# armedbase.net
KiCad netlist of a schematic drawn in EAGLE
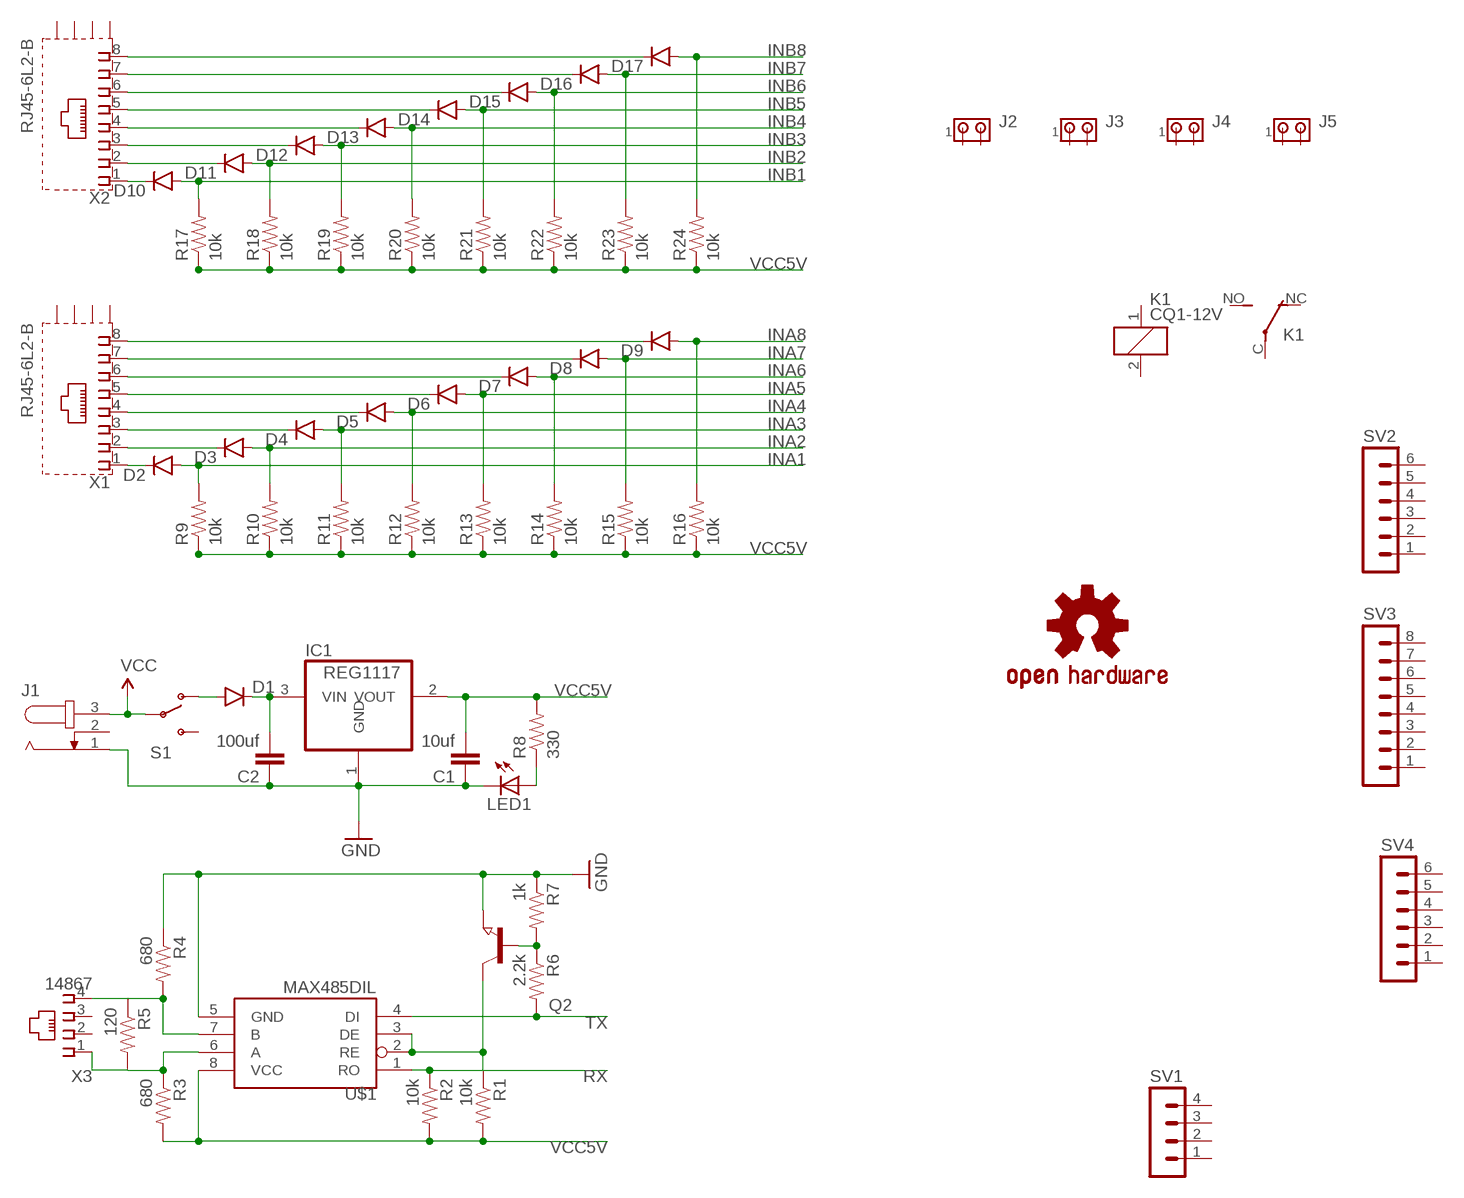
[diagram p0: schematic, sheet 1]

(export (version "E")
  (design (tool "Eeschema 10.0.6"))
  (components
    (comp (ref "C1")
      (value "10uf")
      (footprint "eagle-import:0805")
      (libsource (lib "eagle-import") (part "CAP0805"))
    )
    (comp (ref "C2")
      (value "100uf")
      (footprint "eagle-import:0805")
      (libsource (lib "eagle-import") (part "CAP0805"))
    )
    (comp (ref "D1")
      (value "DIODESMA")
      (footprint "eagle-import:SMA-DIODE")
      (libsource (lib "eagle-import") (part "DIODESMA"))
    )
    (comp (ref "D2")
      (value "DIODESMA")
      (footprint "eagle-import:SMA-DIODE")
      (libsource (lib "eagle-import") (part "DIODESMA"))
    )
    (comp (ref "D3")
      (value "DIODESMA")
      (footprint "eagle-import:SMA-DIODE")
      (libsource (lib "eagle-import") (part "DIODESMA"))
    )
    (comp (ref "D4")
      (value "DIODESMA")
      (footprint "eagle-import:SMA-DIODE")
      (libsource (lib "eagle-import") (part "DIODESMA"))
    )
    (comp (ref "D5")
      (value "DIODESMA")
      (footprint "eagle-import:SMA-DIODE")
      (libsource (lib "eagle-import") (part "DIODESMA"))
    )
    (comp (ref "D6")
      (value "DIODESMA")
      (footprint "eagle-import:SMA-DIODE")
      (libsource (lib "eagle-import") (part "DIODESMA"))
    )
    (comp (ref "D7")
      (value "DIODESMA")
      (footprint "eagle-import:SMA-DIODE")
      (libsource (lib "eagle-import") (part "DIODESMA"))
    )
    (comp (ref "D8")
      (value "DIODESMA")
      (footprint "eagle-import:SMA-DIODE")
      (libsource (lib "eagle-import") (part "DIODESMA"))
    )
    (comp (ref "D9")
      (value "DIODESMA")
      (footprint "eagle-import:SMA-DIODE")
      (libsource (lib "eagle-import") (part "DIODESMA"))
    )
    (comp (ref "D10")
      (value "DIODESMA")
      (footprint "eagle-import:SMA-DIODE")
      (libsource (lib "eagle-import") (part "DIODESMA"))
    )
    (comp (ref "D11")
      (value "DIODESMA")
      (footprint "eagle-import:SMA-DIODE")
      (libsource (lib "eagle-import") (part "DIODESMA"))
    )
    (comp (ref "D12")
      (value "DIODESMA")
      (footprint "eagle-import:SMA-DIODE")
      (libsource (lib "eagle-import") (part "DIODESMA"))
    )
    (comp (ref "D13")
      (value "DIODESMA")
      (footprint "eagle-import:SMA-DIODE")
      (libsource (lib "eagle-import") (part "DIODESMA"))
    )
    (comp (ref "D14")
      (value "DIODESMA")
      (footprint "eagle-import:SMA-DIODE")
      (libsource (lib "eagle-import") (part "DIODESMA"))
    )
    (comp (ref "D15")
      (value "DIODESMA")
      (footprint "eagle-import:SMA-DIODE")
      (libsource (lib "eagle-import") (part "DIODESMA"))
    )
    (comp (ref "D16")
      (value "DIODESMA")
      (footprint "eagle-import:SMA-DIODE")
      (libsource (lib "eagle-import") (part "DIODESMA"))
    )
    (comp (ref "D17")
      (value "DIODESMA")
      (footprint "eagle-import:SMA-DIODE")
      (libsource (lib "eagle-import") (part "DIODESMA"))
    )
    (comp (ref "IC1")
      (value "REG1117")
      (footprint "eagle-import:SOT223")
      (libsource (lib "eagle-import") (part "REG1117"))
    )
    (comp (ref "J1")
      (value "JACK-PLUG1")
      (footprint "eagle-import:SPC4078")
      (libsource (lib "eagle-import") (part "JACK-PLUG1"))
    )
    (comp (ref "J2")
      (value "MTA02-156")
      (footprint "eagle-import:1X2MTA")
      (libsource (lib "eagle-import") (part "MTA02-156"))
    )
    (comp (ref "J3")
      (value "MTA02-156")
      (footprint "eagle-import:1X2MTA")
      (libsource (lib "eagle-import") (part "MTA02-156"))
    )
    (comp (ref "J4")
      (value "MTA02-156")
      (footprint "eagle-import:1X2MTA")
      (libsource (lib "eagle-import") (part "MTA02-156"))
    )
    (comp (ref "J5")
      (value "MTA02-156")
      (footprint "eagle-import:1X2MTA")
      (libsource (lib "eagle-import") (part "MTA02-156"))
    )
    (comp (ref "K1")
      (value "CQ1-12V")
      (footprint "eagle-import:CQ1")
      (libsource (lib "eagle-import") (part "CQ1-12V"))
    )
    (comp (ref "LED1")
      (value "LEDCHIP-LED0805")
      (footprint "eagle-import:CHIP-LED0805")
      (libsource (lib "eagle-import") (part "LEDCHIP-LED0805"))
    )
    (comp (ref "LOGO2")
      (value "OSHW-LOGOL")
      (footprint "eagle-import:OSHW-LOGO-L")
      (libsource (lib "eagle-import") (part "OSHW-LOGOL"))
    )
    (comp (ref "Q2")
      (value "NPN-TRANSISTOR_SOT23")
      (footprint "eagle-import:SOT23")
      (libsource (lib "eagle-import") (part "NPN-TRANSISTOR_SOT23"))
    )
    (comp (ref "R1")
      (value "10k")
      (footprint "eagle-import:0805")
      (libsource (lib "eagle-import") (part "RESISTOR0805-RES"))
    )
    (comp (ref "R2")
      (value "10k")
      (footprint "eagle-import:0805")
      (libsource (lib "eagle-import") (part "RESISTOR0805-RES"))
    )
    (comp (ref "R3")
      (value "680")
      (footprint "eagle-import:0805")
      (libsource (lib "eagle-import") (part "RESISTOR0805-RES"))
    )
    (comp (ref "R4")
      (value "680")
      (footprint "eagle-import:0805")
      (libsource (lib "eagle-import") (part "RESISTOR0805-RES"))
    )
    (comp (ref "R5")
      (value "120")
      (footprint "eagle-import:0805")
      (libsource (lib "eagle-import") (part "RESISTOR0805-RES"))
    )
    (comp (ref "R6")
      (value "2.2k")
      (footprint "eagle-import:0805")
      (libsource (lib "eagle-import") (part "RESISTOR0805-RES"))
    )
    (comp (ref "R7")
      (value "1k")
      (footprint "eagle-import:0805")
      (libsource (lib "eagle-import") (part "RESISTOR0805-RES"))
    )
    (comp (ref "R8")
      (value "330")
      (footprint "eagle-import:0805")
      (libsource (lib "eagle-import") (part "RESISTOR0805-RES"))
    )
    (comp (ref "R9")
      (value "10k")
      (footprint "eagle-import:0805")
      (libsource (lib "eagle-import") (part "RESISTOR0805-RES"))
    )
    (comp (ref "R10")
      (value "10k")
      (footprint "eagle-import:0805")
      (libsource (lib "eagle-import") (part "RESISTOR0805-RES"))
    )
    (comp (ref "R11")
      (value "10k")
      (footprint "eagle-import:0805")
      (libsource (lib "eagle-import") (part "RESISTOR0805-RES"))
    )
    (comp (ref "R12")
      (value "10k")
      (footprint "eagle-import:0805")
      (libsource (lib "eagle-import") (part "RESISTOR0805-RES"))
    )
    (comp (ref "R13")
      (value "10k")
      (footprint "eagle-import:0805")
      (libsource (lib "eagle-import") (part "RESISTOR0805-RES"))
    )
    (comp (ref "R14")
      (value "10k")
      (footprint "eagle-import:0805")
      (libsource (lib "eagle-import") (part "RESISTOR0805-RES"))
    )
    (comp (ref "R15")
      (value "10k")
      (footprint "eagle-import:0805")
      (libsource (lib "eagle-import") (part "RESISTOR0805-RES"))
    )
    (comp (ref "R16")
      (value "10k")
      (footprint "eagle-import:0805")
      (libsource (lib "eagle-import") (part "RESISTOR0805-RES"))
    )
    (comp (ref "R17")
      (value "10k")
      (footprint "eagle-import:0805")
      (libsource (lib "eagle-import") (part "RESISTOR0805-RES"))
    )
    (comp (ref "R18")
      (value "10k")
      (footprint "eagle-import:0805")
      (libsource (lib "eagle-import") (part "RESISTOR0805-RES"))
    )
    (comp (ref "R19")
      (value "10k")
      (footprint "eagle-import:0805")
      (libsource (lib "eagle-import") (part "RESISTOR0805-RES"))
    )
    (comp (ref "R20")
      (value "10k")
      (footprint "eagle-import:0805")
      (libsource (lib "eagle-import") (part "RESISTOR0805-RES"))
    )
    (comp (ref "R21")
      (value "10k")
      (footprint "eagle-import:0805")
      (libsource (lib "eagle-import") (part "RESISTOR0805-RES"))
    )
    (comp (ref "R22")
      (value "10k")
      (footprint "eagle-import:0805")
      (libsource (lib "eagle-import") (part "RESISTOR0805-RES"))
    )
    (comp (ref "R23")
      (value "10k")
      (footprint "eagle-import:0805")
      (libsource (lib "eagle-import") (part "RESISTOR0805-RES"))
    )
    (comp (ref "R24")
      (value "10k")
      (footprint "eagle-import:0805")
      (libsource (lib "eagle-import") (part "RESISTOR0805-RES"))
    )
    (comp (ref "S1")
      (value "SWITCH-SPDTSMD2")
      (footprint "eagle-import:SWITCH-SPDT-SMD")
      (libsource (lib "eagle-import") (part "SWITCH-SPDTSMD2"))
    )
    (comp (ref "SV1")
      (value "MA04-1")
      (footprint "eagle-import:MA04-1")
      (libsource (lib "eagle-import") (part "MA04-1"))
    )
    (comp (ref "SV2")
      (value "MA06-1")
      (footprint "eagle-import:MA06-1")
      (libsource (lib "eagle-import") (part "MA06-1"))
    )
    (comp (ref "SV3")
      (value "MA08-1")
      (footprint "eagle-import:MA08-1")
      (libsource (lib "eagle-import") (part "MA08-1"))
    )
    (comp (ref "SV4")
      (value "MA06-1")
      (footprint "eagle-import:MA06-1")
      (libsource (lib "eagle-import") (part "MA06-1"))
    )
    (comp (ref "U$1")
      (value "MAX485DIL")
      (footprint "eagle-import:DIL08")
      (libsource (lib "eagle-import") (part "MAX485DIL"))
    )
    (comp (ref "X1")
      (value "RJ45-6L2-B")
      (footprint "eagle-import:RJ45-SHIELD2")
      (libsource (lib "eagle-import") (part "RJ452-B-6L"))
    )
    (comp (ref "X2")
      (value "RJ45-6L2-B")
      (footprint "eagle-import:RJ45-SHIELD2")
      (libsource (lib "eagle-import") (part "RJ452-B-6L"))
    )
    (comp (ref "X3")
      (value "14867")
      (footprint "eagle-import:14867")
      (libsource (lib "eagle-import") (part "14867"))
    )
  )
  (nets
    (net (code "1") (name "/INA1") (class "Default")
      (node (ref "D2") (pin "A") (pinfunction "A_A") (pintype "passive"))
      (node (ref "R9") (pin "2") (pinfunction "2_2") (pintype "passive"))
    )
    (net (code "2") (name "/INA2") (class "Default")
      (node (ref "D3") (pin "A") (pinfunction "A_A") (pintype "passive"))
      (node (ref "R10") (pin "2") (pinfunction "2_2") (pintype "passive"))
    )
    (net (code "3") (name "/INA3") (class "Default")
      (node (ref "D4") (pin "A") (pinfunction "A_A") (pintype "passive"))
      (node (ref "R11") (pin "2") (pinfunction "2_2") (pintype "passive"))
    )
    (net (code "4") (name "/INA4") (class "Default")
      (node (ref "D5") (pin "A") (pinfunction "A_A") (pintype "passive"))
      (node (ref "R12") (pin "2") (pinfunction "2_2") (pintype "passive"))
    )
    (net (code "5") (name "/INA5") (class "Default")
      (node (ref "D6") (pin "A") (pinfunction "A_A") (pintype "passive"))
      (node (ref "R13") (pin "2") (pinfunction "2_2") (pintype "passive"))
    )
    (net (code "6") (name "/INA6") (class "Default")
      (node (ref "D7") (pin "A") (pinfunction "A_A") (pintype "passive"))
      (node (ref "R14") (pin "2") (pinfunction "2_2") (pintype "passive"))
    )
    (net (code "7") (name "/INA7") (class "Default")
      (node (ref "D8") (pin "A") (pinfunction "A_A") (pintype "passive"))
      (node (ref "R15") (pin "2") (pinfunction "2_2") (pintype "passive"))
    )
    (net (code "8") (name "/INA8") (class "Default")
      (node (ref "D9") (pin "A") (pinfunction "A_A") (pintype "passive"))
      (node (ref "R16") (pin "2") (pinfunction "2_2") (pintype "passive"))
    )
    (net (code "9") (name "/INB1") (class "Default")
      (node (ref "D10") (pin "A") (pinfunction "A_A") (pintype "passive"))
      (node (ref "R17") (pin "2") (pinfunction "2_2") (pintype "passive"))
    )
    (net (code "10") (name "/INB2") (class "Default")
      (node (ref "D11") (pin "A") (pinfunction "A_A") (pintype "passive"))
      (node (ref "R18") (pin "2") (pinfunction "2_2") (pintype "passive"))
    )
    (net (code "11") (name "/INB3") (class "Default")
      (node (ref "D12") (pin "A") (pinfunction "A_A") (pintype "passive"))
      (node (ref "R19") (pin "2") (pinfunction "2_2") (pintype "passive"))
    )
    (net (code "12") (name "/INB4") (class "Default")
      (node (ref "D13") (pin "A") (pinfunction "A_A") (pintype "passive"))
      (node (ref "R20") (pin "2") (pinfunction "2_2") (pintype "passive"))
    )
    (net (code "13") (name "/INB5") (class "Default")
      (node (ref "D14") (pin "A") (pinfunction "A_A") (pintype "passive"))
      (node (ref "R21") (pin "2") (pinfunction "2_2") (pintype "passive"))
    )
    (net (code "14") (name "/INB6") (class "Default")
      (node (ref "D15") (pin "A") (pinfunction "A_A") (pintype "passive"))
      (node (ref "R22") (pin "2") (pinfunction "2_2") (pintype "passive"))
    )
    (net (code "15") (name "/INB7") (class "Default")
      (node (ref "D16") (pin "A") (pinfunction "A_A") (pintype "passive"))
      (node (ref "R23") (pin "2") (pinfunction "2_2") (pintype "passive"))
    )
    (net (code "16") (name "/INB8") (class "Default")
      (node (ref "D17") (pin "A") (pinfunction "A_A") (pintype "passive"))
      (node (ref "R24") (pin "2") (pinfunction "2_2") (pintype "passive"))
    )
    (net (code "17") (name "/RX") (class "Default")
      (node (ref "R2") (pin "1") (pinfunction "1_1") (pintype "passive"))
      (node (ref "U$1") (pin "1") (pinfunction "RO_1") (pintype "bidirectional"))
    )
    (net (code "18") (name "/TX") (class "Default")
      (node (ref "R6") (pin "2") (pinfunction "2_2") (pintype "passive"))
      (node (ref "U$1") (pin "4") (pinfunction "DI_4") (pintype "bidirectional"))
    )
    (net (code "19") (name "/VCC5V") (class "Default")
      (node (ref "C1") (pin "2") (pinfunction "2_2") (pintype "passive"))
      (node (ref "IC1") (pin "2") (pinfunction "VOUT_2") (pintype "output"))
      (node (ref "R1") (pin "2") (pinfunction "2_2") (pintype "passive"))
      (node (ref "R10") (pin "1") (pinfunction "1_1") (pintype "passive"))
      (node (ref "R11") (pin "1") (pinfunction "1_1") (pintype "passive"))
      (node (ref "R12") (pin "1") (pinfunction "1_1") (pintype "passive"))
      (node (ref "R13") (pin "1") (pinfunction "1_1") (pintype "passive"))
      (node (ref "R14") (pin "1") (pinfunction "1_1") (pintype "passive"))
      (node (ref "R15") (pin "1") (pinfunction "1_1") (pintype "passive"))
      (node (ref "R16") (pin "1") (pinfunction "1_1") (pintype "passive"))
      (node (ref "R17") (pin "1") (pinfunction "1_1") (pintype "passive"))
      (node (ref "R18") (pin "1") (pinfunction "1_1") (pintype "passive"))
      (node (ref "R19") (pin "1") (pinfunction "1_1") (pintype "passive"))
      (node (ref "R2") (pin "2") (pinfunction "2_2") (pintype "passive"))
      (node (ref "R20") (pin "1") (pinfunction "1_1") (pintype "passive"))
      (node (ref "R21") (pin "1") (pinfunction "1_1") (pintype "passive"))
      (node (ref "R22") (pin "1") (pinfunction "1_1") (pintype "passive"))
      (node (ref "R23") (pin "1") (pinfunction "1_1") (pintype "passive"))
      (node (ref "R24") (pin "1") (pinfunction "1_1") (pintype "passive"))
      (node (ref "R3") (pin "2") (pinfunction "2_2") (pintype "passive"))
      (node (ref "R8") (pin "2") (pinfunction "2_2") (pintype "passive"))
      (node (ref "R9") (pin "1") (pinfunction "1_1") (pintype "passive"))
      (node (ref "U$1") (pin "8") (pinfunction "VCC_8") (pintype "bidirectional"))
    )
    (net (code "20") (name "GND") (class "Default")
      (node (ref "C1") (pin "1") (pinfunction "1_1") (pintype "passive"))
      (node (ref "C2") (pin "1") (pinfunction "1_1") (pintype "passive"))
      (node (ref "IC1") (pin "1") (pinfunction "GND_1") (pintype "power_in"))
      (node (ref "J1") (pin "1") (pinfunction "1_1") (pintype "passive"))
      (node (ref "LED1") (pin "C") (pinfunction "C_C") (pintype "passive"))
      (node (ref "Q2") (pin "2") (pinfunction "E_2") (pintype "passive"))
      (node (ref "R4") (pin "1") (pinfunction "1_1") (pintype "passive"))
      (node (ref "R7") (pin "1") (pinfunction "1_1") (pintype "passive"))
      (node (ref "U$1") (pin "5") (pinfunction "GND_5") (pintype "bidirectional"))
    )
    (net (code "21") (name "Net-(D2-PadC)") (class "Default")
      (node (ref "D2") (pin "C") (pinfunction "C_C") (pintype "passive"))
      (node (ref "X1") (pin "1") (pinfunction "1_1") (pintype "passive"))
    )
    (net (code "22") (name "Net-(D3-PadC)") (class "Default")
      (node (ref "D3") (pin "C") (pinfunction "C_C") (pintype "passive"))
      (node (ref "X1") (pin "2") (pinfunction "2_2") (pintype "passive"))
    )
    (net (code "23") (name "Net-(D4-PadC)") (class "Default")
      (node (ref "D4") (pin "C") (pinfunction "C_C") (pintype "passive"))
      (node (ref "X1") (pin "3") (pinfunction "3_3") (pintype "passive"))
    )
    (net (code "24") (name "Net-(D5-PadC)") (class "Default")
      (node (ref "D5") (pin "C") (pinfunction "C_C") (pintype "passive"))
      (node (ref "X1") (pin "4") (pinfunction "4_4") (pintype "passive"))
    )
    (net (code "25") (name "Net-(D6-PadC)") (class "Default")
      (node (ref "D6") (pin "C") (pinfunction "C_C") (pintype "passive"))
      (node (ref "X1") (pin "5") (pinfunction "5_5") (pintype "passive"))
    )
    (net (code "26") (name "Net-(D7-PadC)") (class "Default")
      (node (ref "D7") (pin "C") (pinfunction "C_C") (pintype "passive"))
      (node (ref "X1") (pin "6") (pinfunction "6_6") (pintype "passive"))
    )
    (net (code "27") (name "Net-(D8-PadC)") (class "Default")
      (node (ref "D8") (pin "C") (pinfunction "C_C") (pintype "passive"))
      (node (ref "X1") (pin "7") (pinfunction "7_7") (pintype "passive"))
    )
    (net (code "28") (name "Net-(D9-PadC)") (class "Default")
      (node (ref "D9") (pin "C") (pinfunction "C_C") (pintype "passive"))
      (node (ref "X1") (pin "8") (pinfunction "8_8") (pintype "passive"))
    )
    (net (code "29") (name "Net-(D10-PadC)") (class "Default")
      (node (ref "D10") (pin "C") (pinfunction "C_C") (pintype "passive"))
      (node (ref "X2") (pin "1") (pinfunction "1_1") (pintype "passive"))
    )
    (net (code "30") (name "Net-(D11-PadC)") (class "Default")
      (node (ref "D11") (pin "C") (pinfunction "C_C") (pintype "passive"))
      (node (ref "X2") (pin "2") (pinfunction "2_2") (pintype "passive"))
    )
    (net (code "31") (name "Net-(D12-PadC)") (class "Default")
      (node (ref "D12") (pin "C") (pinfunction "C_C") (pintype "passive"))
      (node (ref "X2") (pin "3") (pinfunction "3_3") (pintype "passive"))
    )
    (net (code "32") (name "Net-(D13-PadC)") (class "Default")
      (node (ref "D13") (pin "C") (pinfunction "C_C") (pintype "passive"))
      (node (ref "X2") (pin "4") (pinfunction "4_4") (pintype "passive"))
    )
    (net (code "33") (name "Net-(D14-PadC)") (class "Default")
      (node (ref "D14") (pin "C") (pinfunction "C_C") (pintype "passive"))
      (node (ref "X2") (pin "5") (pinfunction "5_5") (pintype "passive"))
    )
    (net (code "34") (name "Net-(D15-PadC)") (class "Default")
      (node (ref "D15") (pin "C") (pinfunction "C_C") (pintype "passive"))
      (node (ref "X2") (pin "6") (pinfunction "6_6") (pintype "passive"))
    )
    (net (code "35") (name "Net-(D16-PadC)") (class "Default")
      (node (ref "D16") (pin "C") (pinfunction "C_C") (pintype "passive"))
      (node (ref "X2") (pin "7") (pinfunction "7_7") (pintype "passive"))
    )
    (net (code "36") (name "Net-(D17-PadC)") (class "Default")
      (node (ref "D17") (pin "C") (pinfunction "C_C") (pintype "passive"))
      (node (ref "X2") (pin "8") (pinfunction "8_8") (pintype "passive"))
    )
    (net (code "37") (name "Net-(IC1-VIN)") (class "Default")
      (node (ref "C2") (pin "2") (pinfunction "2_2") (pintype "passive"))
      (node (ref "D1") (pin "C") (pinfunction "C_C") (pintype "passive"))
      (node (ref "IC1") (pin "3") (pinfunction "VIN_3") (pintype "input"))
    )
    (net (code "38") (name "Net-(LED1-PadA)") (class "Default")
      (node (ref "LED1") (pin "A") (pinfunction "A_A") (pintype "passive"))
      (node (ref "R8") (pin "1") (pinfunction "1_1") (pintype "passive"))
    )
    (net (code "39") (name "Net-(Q2-B)") (class "Default")
      (node (ref "Q2") (pin "1") (pinfunction "B_1") (pintype "passive"))
      (node (ref "R6") (pin "1") (pinfunction "1_1") (pintype "passive"))
      (node (ref "R7") (pin "2") (pinfunction "2_2") (pintype "passive"))
    )
    (net (code "40") (name "Net-(Q2-C)") (class "Default")
      (node (ref "Q2") (pin "3") (pinfunction "C_3") (pintype "passive"))
      (node (ref "R1") (pin "1") (pinfunction "1_1") (pintype "passive"))
      (node (ref "U$1") (pin "2") (pinfunction "RE_2") (pintype "bidirectional"))
      (node (ref "U$1") (pin "3") (pinfunction "DE_3") (pintype "bidirectional"))
    )
    (net (code "41") (name "Net-(S1-O)") (class "Default")
      (node (ref "D1") (pin "A") (pinfunction "A_A") (pintype "passive"))
      (node (ref "S1") (pin "1") (pinfunction "O_1") (pintype "passive"))
    )
    (net (code "42") (name "Net-(U$1-A)") (class "Default")
      (node (ref "R3") (pin "1") (pinfunction "1_1") (pintype "passive"))
      (node (ref "R5") (pin "2") (pinfunction "2_2") (pintype "passive"))
      (node (ref "U$1") (pin "6") (pinfunction "A_6") (pintype "bidirectional"))
      (node (ref "X3") (pin "1") (pinfunction "1_1") (pintype "passive"))
    )
    (net (code "43") (name "Net-(U$1-B)") (class "Default")
      (node (ref "R4") (pin "2") (pinfunction "2_2") (pintype "passive"))
      (node (ref "R5") (pin "1") (pinfunction "1_1") (pintype "passive"))
      (node (ref "U$1") (pin "7") (pinfunction "B_7") (pintype "bidirectional"))
      (node (ref "X3") (pin "4") (pinfunction "4_4") (pintype "passive"))
    )
    (net (code "44") (name "VCC") (class "Default")
      (node (ref "J1") (pin "3") (pinfunction "3_3") (pintype "passive"))
      (node (ref "S1") (pin "2") (pinfunction "P_2") (pintype "passive"))
    )
    (net (code "45") (name "unconnected-(J1-Pad2)") (class "Default")
      (node (ref "J1") (pin "2") (pinfunction "2_2") (pintype "passive"))
    )
    (net (code "46") (name "unconnected-(J2-Pad1)") (class "Default")
      (node (ref "J2") (pin "1") (pinfunction "1_1") (pintype "passive"))
    )
    (net (code "47") (name "unconnected-(J2-Pad2)") (class "Default")
      (node (ref "J2") (pin "2") (pinfunction "2_2") (pintype "passive"))
    )
    (net (code "48") (name "unconnected-(J3-Pad1)") (class "Default")
      (node (ref "J3") (pin "1") (pinfunction "1_1") (pintype "passive"))
    )
    (net (code "49") (name "unconnected-(J3-Pad2)") (class "Default")
      (node (ref "J3") (pin "2") (pinfunction "2_2") (pintype "passive"))
    )
    (net (code "50") (name "unconnected-(J4-Pad1)") (class "Default")
      (node (ref "J4") (pin "1") (pinfunction "1_1") (pintype "passive"))
    )
    (net (code "51") (name "unconnected-(J4-Pad2)") (class "Default")
      (node (ref "J4") (pin "2") (pinfunction "2_2") (pintype "passive"))
    )
    (net (code "52") (name "unconnected-(J5-Pad1)") (class "Default")
      (node (ref "J5") (pin "1") (pinfunction "1_1") (pintype "passive"))
    )
    (net (code "53") (name "unconnected-(J5-Pad2)") (class "Default")
      (node (ref "J5") (pin "2") (pinfunction "2_2") (pintype "passive"))
    )
    (net (code "54") (name "unconnected-(K1-Pad1)") (class "Default")
      (node (ref "K1") (pin "1") (pinfunction "1_1") (pintype "passive"))
    )
    (net (code "55") (name "unconnected-(K1-Pad2)") (class "Default")
      (node (ref "K1") (pin "2") (pinfunction "2_2") (pintype "passive"))
    )
    (net (code "56") (name "unconnected-(K1B-O-PadNC)") (class "Default")
      (node (ref "K1") (pin "NC") (pinfunction "O_NC") (pintype "passive"))
    )
    (net (code "57") (name "unconnected-(K1B-P-PadC)") (class "Default")
      (node (ref "K1") (pin "C") (pinfunction "P_C") (pintype "passive"))
    )
    (net (code "58") (name "unconnected-(K1B-S-PadNO)") (class "Default")
      (node (ref "K1") (pin "NO") (pinfunction "S_NO") (pintype "passive"))
    )
    (net (code "59") (name "unconnected-(S1-S-Pad3)") (class "Default")
      (node (ref "S1") (pin "3") (pinfunction "S_3") (pintype "passive"))
    )
    (net (code "60") (name "unconnected-(SV1-Pad1)") (class "Default")
      (node (ref "SV1") (pin "1") (pinfunction "1_1") (pintype "passive"))
    )
    (net (code "61") (name "unconnected-(SV1-Pad2)") (class "Default")
      (node (ref "SV1") (pin "2") (pinfunction "2_2") (pintype "passive"))
    )
    (net (code "62") (name "unconnected-(SV1-Pad3)") (class "Default")
      (node (ref "SV1") (pin "3") (pinfunction "3_3") (pintype "passive"))
    )
    (net (code "63") (name "unconnected-(SV1-Pad4)") (class "Default")
      (node (ref "SV1") (pin "4") (pinfunction "4_4") (pintype "passive"))
    )
    (net (code "64") (name "unconnected-(SV2-Pad1)") (class "Default")
      (node (ref "SV2") (pin "1") (pinfunction "1_1") (pintype "passive"))
    )
    (net (code "65") (name "unconnected-(SV2-Pad2)") (class "Default")
      (node (ref "SV2") (pin "2") (pinfunction "2_2") (pintype "passive"))
    )
    (net (code "66") (name "unconnected-(SV2-Pad3)") (class "Default")
      (node (ref "SV2") (pin "3") (pinfunction "3_3") (pintype "passive"))
    )
    (net (code "67") (name "unconnected-(SV2-Pad4)") (class "Default")
      (node (ref "SV2") (pin "4") (pinfunction "4_4") (pintype "passive"))
    )
    (net (code "68") (name "unconnected-(SV2-Pad5)") (class "Default")
      (node (ref "SV2") (pin "5") (pinfunction "5_5") (pintype "passive"))
    )
    (net (code "69") (name "unconnected-(SV2-Pad6)") (class "Default")
      (node (ref "SV2") (pin "6") (pinfunction "6_6") (pintype "passive"))
    )
    (net (code "70") (name "unconnected-(SV3-Pad1)") (class "Default")
      (node (ref "SV3") (pin "1") (pinfunction "1_1") (pintype "passive"))
    )
    (net (code "71") (name "unconnected-(SV3-Pad2)") (class "Default")
      (node (ref "SV3") (pin "2") (pinfunction "2_2") (pintype "passive"))
    )
    (net (code "72") (name "unconnected-(SV3-Pad3)") (class "Default")
      (node (ref "SV3") (pin "3") (pinfunction "3_3") (pintype "passive"))
    )
    (net (code "73") (name "unconnected-(SV3-Pad4)") (class "Default")
      (node (ref "SV3") (pin "4") (pinfunction "4_4") (pintype "passive"))
    )
    (net (code "74") (name "unconnected-(SV3-Pad5)") (class "Default")
      (node (ref "SV3") (pin "5") (pinfunction "5_5") (pintype "passive"))
    )
    (net (code "75") (name "unconnected-(SV3-Pad6)") (class "Default")
      (node (ref "SV3") (pin "6") (pinfunction "6_6") (pintype "passive"))
    )
    (net (code "76") (name "unconnected-(SV3-Pad7)") (class "Default")
      (node (ref "SV3") (pin "7") (pinfunction "7_7") (pintype "passive"))
    )
    (net (code "77") (name "unconnected-(SV3-Pad8)") (class "Default")
      (node (ref "SV3") (pin "8") (pinfunction "8_8") (pintype "passive"))
    )
    (net (code "78") (name "unconnected-(SV4-Pad1)") (class "Default")
      (node (ref "SV4") (pin "1") (pinfunction "1_1") (pintype "passive"))
    )
    (net (code "79") (name "unconnected-(SV4-Pad2)") (class "Default")
      (node (ref "SV4") (pin "2") (pinfunction "2_2") (pintype "passive"))
    )
    (net (code "80") (name "unconnected-(SV4-Pad3)") (class "Default")
      (node (ref "SV4") (pin "3") (pinfunction "3_3") (pintype "passive"))
    )
    (net (code "81") (name "unconnected-(SV4-Pad4)") (class "Default")
      (node (ref "SV4") (pin "4") (pinfunction "4_4") (pintype "passive"))
    )
    (net (code "82") (name "unconnected-(SV4-Pad5)") (class "Default")
      (node (ref "SV4") (pin "5") (pinfunction "5_5") (pintype "passive"))
    )
    (net (code "83") (name "unconnected-(SV4-Pad6)") (class "Default")
      (node (ref "SV4") (pin "6") (pinfunction "6_6") (pintype "passive"))
    )
    (net (code "84") (name "unconnected-(X1-S-PadS1)") (class "Default")
      (node (ref "X1") (pin "S1") (pinfunction "S_S1") (pintype "passive"))
    )
    (net (code "85") (name "unconnected-(X1-S-PadS2)") (class "Default")
      (node (ref "X1") (pin "S2") (pinfunction "S_S2") (pintype "passive"))
    )
    (net (code "86") (name "unconnected-(X1-S-PadS3)") (class "Default")
      (node (ref "X1") (pin "S3") (pinfunction "S_S3") (pintype "passive"))
    )
    (net (code "87") (name "unconnected-(X1-S-PadS4)") (class "Default")
      (node (ref "X1") (pin "S4") (pinfunction "S_S4") (pintype "passive"))
    )
    (net (code "88") (name "unconnected-(X2-S-PadS1)") (class "Default")
      (node (ref "X2") (pin "S1") (pinfunction "S_S1") (pintype "passive"))
    )
    (net (code "89") (name "unconnected-(X2-S-PadS2)") (class "Default")
      (node (ref "X2") (pin "S2") (pinfunction "S_S2") (pintype "passive"))
    )
    (net (code "90") (name "unconnected-(X2-S-PadS3)") (class "Default")
      (node (ref "X2") (pin "S3") (pinfunction "S_S3") (pintype "passive"))
    )
    (net (code "91") (name "unconnected-(X2-S-PadS4)") (class "Default")
      (node (ref "X2") (pin "S4") (pinfunction "S_S4") (pintype "passive"))
    )
    (net (code "92") (name "unconnected-(X3-Pad2)") (class "Default")
      (node (ref "X3") (pin "2") (pinfunction "2_2") (pintype "passive"))
    )
    (net (code "93") (name "unconnected-(X3-Pad3)") (class "Default")
      (node (ref "X3") (pin "3") (pinfunction "3_3") (pintype "passive"))
    )
  )
)
